# Decawave.net
KiCad netlist of a schematic drawn in Altium Designer
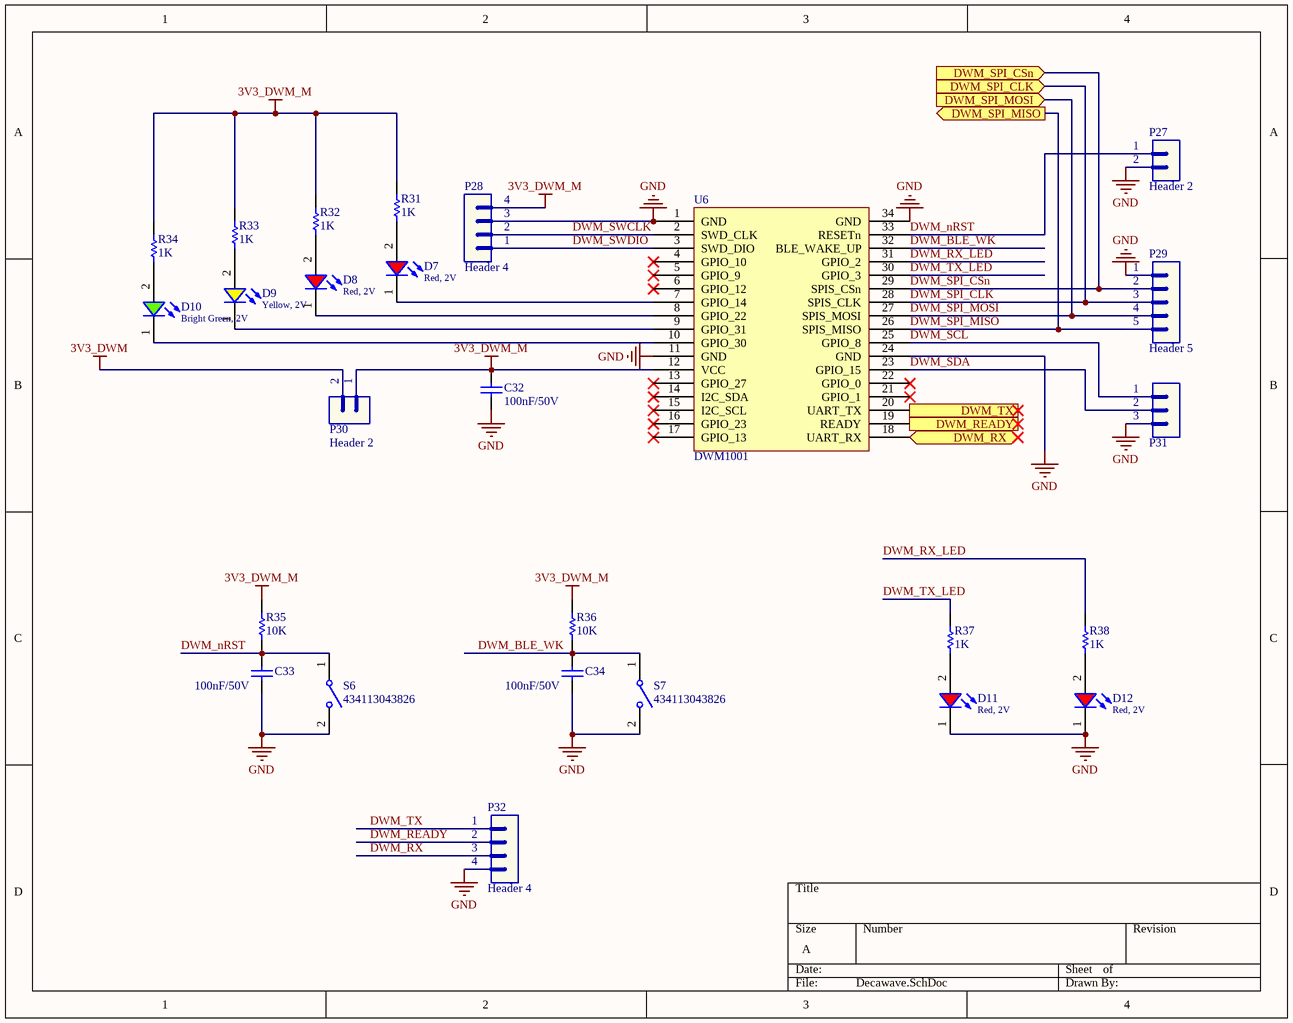
[diagram p0: Decawave.SchDoc]

(export (version "E")
  (design (tool "Eeschema 10.0.6"))
  (components
    (comp (ref "C32")
      (value "100nF/50V")
      (footprint "CAP-SM-0805")
      (description "CAP CER 0.1UF 50V Y5V 0805")
      (fields
        (field (name "MANUFACTURER") "Samsung Electro-Mechanics")
        (field (name "MANUFACTURER PART NUMBER") "CL21F104ZBCNNNC")
      )
      (libsource (lib "Capacitor") (part "Cap-100nF-50V-0805"))
    )
    (comp (ref "C33")
      (value "100nF/50V")
      (footprint "CAP-SM-0805")
      (description "CAP CER 0.1UF 50V Y5V 0805")
      (fields
        (field (name "MANUFACTURER") "Samsung Electro-Mechanics")
        (field (name "MANUFACTURER PART NUMBER") "CL21F104ZBCNNNC")
      )
      (libsource (lib "Capacitor") (part "Cap-100nF-50V-0805"))
    )
    (comp (ref "C34")
      (value "100nF/50V")
      (footprint "CAP-SM-0805")
      (description "CAP CER 0.1UF 50V Y5V 0805")
      (fields
        (field (name "MANUFACTURER") "Samsung Electro-Mechanics")
        (field (name "MANUFACTURER PART NUMBER") "CL21F104ZBCNNNC")
      )
      (libsource (lib "Capacitor") (part "Cap-100nF-50V-0805"))
    )
    (comp (ref "D7")
      (value "Red, 2V")
      (footprint "WL-SMCW_0805")
      (description "WL-SMCW SMT Mono-color Chip LED Waterclear, size 0805, Red, 2V, 140deg")
      (fields (field (name "PART NUMBER") "150080RS75000") (field (name "PUBLISHER") "Wurth Elektronik"))
      (libsource (lib "LED_150060BS75000_Altium_WL-SMCW_rev20a") (part "150080RS75000"))
    )
    (comp (ref "D8")
      (value "Red, 2V")
      (footprint "WL-SMCW_0805")
      (description "WL-SMCW SMT Mono-color Chip LED Waterclear, size 0805, Red, 2V, 140deg")
      (fields (field (name "PART NUMBER") "150080RS75000") (field (name "PUBLISHER") "Wurth Elektronik"))
      (libsource (lib "LED_150060BS75000_Altium_WL-SMCW_rev20a") (part "150080RS75000"))
    )
    (comp (ref "D9")
      (value "Yellow, 2V")
      (footprint "WL-SMCW_0805")
      (description "WL-SMCW SMT Mono-color Chip LED Waterclear, size 0805, Yellow, 2V, 140deg")
      (fields (field (name "PART NUMBER") "150080YS75000") (field (name "PUBLISHER") "Wurth Elektronik"))
      (libsource (lib "LED_150060BS75000_Altium_WL-SMCW_rev20a") (part "150080YS75000"))
    )
    (comp (ref "D10")
      (value "Bright Green, 2V")
      (footprint "WL-SMCW_0805")
      (description "WL-SMCW SMT Mono-color Chip LED Waterclear, size 0805, Bright Green, 2V, 140deg")
      (fields (field (name "PART NUMBER") "150080VS75000") (field (name "PUBLISHER") "Wurth Elektronik"))
      (libsource (lib "LED_150060BS75000_Altium_WL-SMCW_rev20a") (part "150080VS75000"))
    )
    (comp (ref "D11")
      (value "Red, 2V")
      (footprint "WL-SMCW_0805")
      (description "WL-SMCW SMT Mono-color Chip LED Waterclear, size 0805, Red, 2V, 140deg")
      (fields (field (name "PART NUMBER") "150080RS75000") (field (name "PUBLISHER") "Wurth Elektronik"))
      (libsource (lib "LED_150060BS75000_Altium_WL-SMCW_rev20a") (part "150080RS75000"))
    )
    (comp (ref "D12")
      (value "Red, 2V")
      (footprint "WL-SMCW_0805")
      (description "WL-SMCW SMT Mono-color Chip LED Waterclear, size 0805, Red, 2V, 140deg")
      (fields (field (name "PART NUMBER") "150080RS75000") (field (name "PUBLISHER") "Wurth Elektronik"))
      (libsource (lib "LED_150060BS75000_Altium_WL-SMCW_rev20a") (part "150080RS75000"))
    )
    (comp (ref "P27")
      (value "Header 2")
      (footprint "JP2")
      (description "Header, 2-Pin")
      (fields (field (name "PUBLISHER") "Altium Limited"))
      (libsource (lib "") (part "Header 2_1"))
    )
    (comp (ref "P28")
      (value "Header 4")
      (footprint "JP4")
      (description "Header, 4-Pin")
      (fields (field (name "PUBLISHER") "Altium Limited"))
      (libsource (lib "Header-connector") (part "Header 4"))
    )
    (comp (ref "P29")
      (value "Header 5")
      (footprint "JP5")
      (description "Header, 5-Pin")
      (fields (field (name "PUBLISHER") "Altium Limited"))
      (libsource (lib "Header-connector") (part "Header 5"))
    )
    (comp (ref "P30")
      (value "Header 2")
      (footprint "JP2")
      (description "Header, 2-Pin")
      (fields (field (name "PUBLISHER") "Altium Limited"))
      (libsource (lib "Header-connector") (part "Header 2"))
    )
    (comp (ref "P31")
      (value "Header 3")
      (footprint "JP3")
      (description "Header, 3-Pin")
      (fields (field (name "PUBLISHER") "Altium Limited"))
      (libsource (lib "Header-connector") (part "Header 3"))
    )
    (comp (ref "P32")
      (value "Header 4")
      (footprint "JP4")
      (description "Header, 4-Pin")
      (fields (field (name "PUBLISHER") "Altium Limited"))
      (libsource (lib "") (part "Header 4_1"))
    )
    (comp (ref "R31")
      (value "1K")
      (footprint "Resistor:RES-SM-0805")
      (description "RES 1K OHM 1% 1/4W 0805")
      (fields
        (field (name "MANUFACTURER") "Stackpole Electronics Inc")
        (field (name "MANUFACTURER PART NUMBER") "RNCP0805FTD1K00")
      )
      (libsource (lib "Resistor") (part "Res-1K-0805"))
    )
    (comp (ref "R32")
      (value "1K")
      (footprint "Resistor:RES-SM-0805")
      (description "RES 1K OHM 1% 1/4W 0805")
      (fields
        (field (name "MANUFACTURER") "Stackpole Electronics Inc")
        (field (name "MANUFACTURER PART NUMBER") "RNCP0805FTD1K00")
      )
      (libsource (lib "Resistor") (part "Res-1K-0805"))
    )
    (comp (ref "R33")
      (value "1K")
      (footprint "Resistor:RES-SM-0805")
      (description "RES 1K OHM 1% 1/4W 0805")
      (fields
        (field (name "MANUFACTURER") "Stackpole Electronics Inc")
        (field (name "MANUFACTURER PART NUMBER") "RNCP0805FTD1K00")
      )
      (libsource (lib "Resistor") (part "Res-1K-0805"))
    )
    (comp (ref "R34")
      (value "1K")
      (footprint "Resistor:RES-SM-0805")
      (description "RES 1K OHM 1% 1/4W 0805")
      (fields
        (field (name "MANUFACTURER") "Stackpole Electronics Inc")
        (field (name "MANUFACTURER PART NUMBER") "RNCP0805FTD1K00")
      )
      (libsource (lib "Resistor") (part "Res-1K-0805"))
    )
    (comp (ref "R35")
      (value "10K")
      (footprint "Resistor:RES-SM-0805")
      (description "RES 10K OHM 1% 1/4W 0805")
      (fields
        (field (name "MANUFACTURER") "Stackpole Electronics Inc")
        (field (name "MANUFACTURER PART NUMBER") "RNCP0805FTD10K0")
      )
      (libsource (lib "Resistor") (part "Res-10k-0805"))
    )
    (comp (ref "R36")
      (value "10K")
      (footprint "Resistor:RES-SM-0805")
      (description "RES 10K OHM 1% 1/4W 0805")
      (fields
        (field (name "MANUFACTURER") "Stackpole Electronics Inc")
        (field (name "MANUFACTURER PART NUMBER") "RNCP0805FTD10K0")
      )
      (libsource (lib "Resistor") (part "Res-10k-0805"))
    )
    (comp (ref "R37")
      (value "1K")
      (footprint "Resistor:RES-SM-0805")
      (description "RES 1K OHM 1% 1/4W 0805")
      (fields
        (field (name "MANUFACTURER") "Stackpole Electronics Inc")
        (field (name "MANUFACTURER PART NUMBER") "RNCP0805FTD1K00")
      )
      (libsource (lib "Resistor") (part "Res-1K-0805"))
    )
    (comp (ref "R38")
      (value "1K")
      (footprint "Resistor:RES-SM-0805")
      (description "RES 1K OHM 1% 1/4W 0805")
      (fields
        (field (name "MANUFACTURER") "Stackpole Electronics Inc")
        (field (name "MANUFACTURER PART NUMBER") "RNCP0805FTD1K00")
      )
      (libsource (lib "Resistor") (part "Res-1K-0805"))
    )
    (comp (ref "S6")
      (value "434113043826")
      (footprint "434113043826")
      (description "WS-TASV J-Bend SMT Tact Switch 6x3.5mm, height 4.3mm, 260gf")
      (fields (field (name "PUBLISHER") "Wurth Elektronik"))
      (libsource (lib "434113043826_Altium_WS-TASV_rev20a") (part "434113043826"))
    )
    (comp (ref "S7")
      (value "434113043826")
      (footprint "434113043826")
      (description "WS-TASV J-Bend SMT Tact Switch 6x3.5mm, height 4.3mm, 260gf")
      (fields (field (name "PUBLISHER") "Wurth Elektronik"))
      (libsource (lib "434113043826_Altium_WS-TASV_rev20a") (part "434113043826"))
    )
    (comp (ref "U6") (value "DWM1001") (footprint "DWM1001") (libsource (lib "PIFWRoBot") (part "DWM1001")))
  )
  (nets
    (net (code "1") (name "/DWM_BLE_WK") (class "Default")
      (node (ref "C34") (pin "1") (pinfunction "1_1") (pintype "passive"))
      (node (ref "R36") (pin "1") (pinfunction "1_1") (pintype "passive"))
      (node (ref "S7") (pin "1") (pinfunction "1_1") (pintype "passive"))
      (node (ref "U6") (pin "32") (pinfunction "BLE_WAKE_UP_32") (pintype "passive"))
    )
    (net (code "2") (name "/DWM_READY") (class "Default")
      (node (ref "P32") (pin "2") (pinfunction "2_2") (pintype "passive+no_connect"))
    )
    (net (code "3") (name "/DWM_RX") (class "Default")
      (node (ref "P32") (pin "3") (pinfunction "3_3") (pintype "passive+no_connect"))
    )
    (net (code "4") (name "/DWM_RX_LED") (class "Default")
      (node (ref "R38") (pin "2") (pinfunction "2_2") (pintype "passive"))
      (node (ref "U6") (pin "31") (pinfunction "GPIO_2_31") (pintype "passive"))
    )
    (net (code "5") (name "/DWM_SCL") (class "Default")
      (node (ref "P31") (pin "1") (pinfunction "1_1") (pintype "passive"))
      (node (ref "U6") (pin "25") (pinfunction "GPIO_8_25") (pintype "passive"))
    )
    (net (code "6") (name "/DWM_SDA") (class "Default")
      (node (ref "P31") (pin "2") (pinfunction "2_2") (pintype "passive"))
      (node (ref "U6") (pin "23") (pinfunction "GPIO_15_23") (pintype "passive"))
    )
    (net (code "7") (name "/DWM_SPI_CLK") (class "Default")
      (node (ref "P29") (pin "3") (pinfunction "3_3") (pintype "passive"))
      (node (ref "U6") (pin "28") (pinfunction "SPIS_CLK_28") (pintype "passive"))
    )
    (net (code "8") (name "/DWM_SPI_CSn") (class "Default")
      (node (ref "P29") (pin "2") (pinfunction "2_2") (pintype "passive"))
      (node (ref "U6") (pin "29") (pinfunction "SPIS_CSn_29") (pintype "passive"))
    )
    (net (code "9") (name "/DWM_SPI_MISO") (class "Default")
      (node (ref "P29") (pin "5") (pinfunction "5_5") (pintype "passive"))
      (node (ref "U6") (pin "26") (pinfunction "SPIS_MISO_26") (pintype "passive"))
    )
    (net (code "10") (name "/DWM_SPI_MOSI") (class "Default")
      (node (ref "P29") (pin "4") (pinfunction "4_4") (pintype "passive"))
      (node (ref "U6") (pin "27") (pinfunction "SPIS_MOSI_27") (pintype "passive"))
    )
    (net (code "11") (name "/DWM_SWCLK") (class "Default")
      (node (ref "P28") (pin "2") (pinfunction "2_2") (pintype "passive"))
      (node (ref "U6") (pin "2") (pinfunction "SWD_CLK_2") (pintype "passive"))
    )
    (net (code "12") (name "/DWM_SWDIO") (class "Default")
      (node (ref "P28") (pin "1") (pinfunction "1_1") (pintype "passive"))
      (node (ref "U6") (pin "3") (pinfunction "SWD_DIO_3") (pintype "passive"))
    )
    (net (code "13") (name "/DWM_TX") (class "Default")
      (node (ref "P32") (pin "1") (pinfunction "1_1") (pintype "passive+no_connect"))
    )
    (net (code "14") (name "/DWM_TX_LED") (class "Default")
      (node (ref "R37") (pin "2") (pinfunction "2_2") (pintype "passive"))
      (node (ref "U6") (pin "30") (pinfunction "GPIO_3_30") (pintype "passive"))
    )
    (net (code "15") (name "/DWM_nRST") (class "Default")
      (node (ref "C33") (pin "1") (pinfunction "1_1") (pintype "passive"))
      (node (ref "P27") (pin "1") (pinfunction "1_1") (pintype "passive"))
      (node (ref "R35") (pin "1") (pinfunction "1_1") (pintype "passive"))
      (node (ref "S6") (pin "1") (pinfunction "1_1") (pintype "passive"))
      (node (ref "U6") (pin "33") (pinfunction "RESETn_33") (pintype "passive"))
    )
    (net (code "16") (name "3V3_DWM") (class "Default")
      (node (ref "P30") (pin "2") (pinfunction "2_2") (pintype "passive"))
    )
    (net (code "17") (name "3V3_DWM_M") (class "Default")
      (node (ref "C32") (pin "2") (pinfunction "2_2") (pintype "passive"))
      (node (ref "P28") (pin "4") (pinfunction "4_4") (pintype "passive"))
      (node (ref "P30") (pin "1") (pinfunction "1_1") (pintype "passive"))
      (node (ref "R31") (pin "2") (pinfunction "2_2") (pintype "passive"))
      (node (ref "R32") (pin "2") (pinfunction "2_2") (pintype "passive"))
      (node (ref "R33") (pin "2") (pinfunction "2_2") (pintype "passive"))
      (node (ref "R34") (pin "2") (pinfunction "2_2") (pintype "passive"))
      (node (ref "R35") (pin "2") (pinfunction "2_2") (pintype "passive"))
      (node (ref "R36") (pin "2") (pinfunction "2_2") (pintype "passive"))
      (node (ref "U6") (pin "12") (pinfunction "VCC_12") (pintype "passive"))
    )
    (net (code "18") (name "GND") (class "Default")
      (node (ref "C32") (pin "1") (pinfunction "1_1") (pintype "passive"))
      (node (ref "C33") (pin "2") (pinfunction "2_2") (pintype "passive"))
      (node (ref "C34") (pin "2") (pinfunction "2_2") (pintype "passive"))
      (node (ref "D11") (pin "1") (pinfunction "K_1") (pintype "passive"))
      (node (ref "D12") (pin "1") (pinfunction "K_1") (pintype "passive"))
      (node (ref "P27") (pin "2") (pinfunction "2_2") (pintype "passive"))
      (node (ref "P28") (pin "3") (pinfunction "3_3") (pintype "passive"))
      (node (ref "P29") (pin "1") (pinfunction "1_1") (pintype "passive"))
      (node (ref "P31") (pin "3") (pinfunction "3_3") (pintype "passive"))
      (node (ref "P32") (pin "4") (pinfunction "4_4") (pintype "passive"))
      (node (ref "S6") (pin "2") (pinfunction "2_2") (pintype "passive"))
      (node (ref "S7") (pin "2") (pinfunction "2_2") (pintype "passive"))
      (node (ref "U6") (pin "1") (pinfunction "GND_1") (pintype "passive"))
      (node (ref "U6") (pin "11") (pinfunction "GND_11") (pintype "passive"))
      (node (ref "U6") (pin "24") (pinfunction "GND_24") (pintype "passive"))
      (node (ref "U6") (pin "34") (pinfunction "GND_34") (pintype "passive"))
    )
    (net (code "19") (name "Net-(D7-A)") (class "Default")
      (node (ref "D7") (pin "2") (pinfunction "A_2") (pintype "passive"))
      (node (ref "R31") (pin "1") (pinfunction "1_1") (pintype "passive"))
    )
    (net (code "20") (name "Net-(D7-K)") (class "Default")
      (node (ref "D7") (pin "1") (pinfunction "K_1") (pintype "passive"))
      (node (ref "U6") (pin "7") (pinfunction "GPIO_14_7") (pintype "passive"))
    )
    (net (code "21") (name "Net-(D8-A)") (class "Default")
      (node (ref "D8") (pin "2") (pinfunction "A_2") (pintype "passive"))
      (node (ref "R32") (pin "1") (pinfunction "1_1") (pintype "passive"))
    )
    (net (code "22") (name "Net-(D8-K)") (class "Default")
      (node (ref "D8") (pin "1") (pinfunction "K_1") (pintype "passive"))
      (node (ref "U6") (pin "8") (pinfunction "GPIO_22_8") (pintype "passive"))
    )
    (net (code "23") (name "Net-(D9-A)") (class "Default")
      (node (ref "D9") (pin "2") (pinfunction "A_2") (pintype "passive"))
      (node (ref "R33") (pin "1") (pinfunction "1_1") (pintype "passive"))
    )
    (net (code "24") (name "Net-(D9-K)") (class "Default")
      (node (ref "D9") (pin "1") (pinfunction "K_1") (pintype "passive"))
      (node (ref "U6") (pin "9") (pinfunction "GPIO_31_9") (pintype "passive"))
    )
    (net (code "25") (name "Net-(D10-A)") (class "Default")
      (node (ref "D10") (pin "2") (pinfunction "A_2") (pintype "passive"))
      (node (ref "R34") (pin "1") (pinfunction "1_1") (pintype "passive"))
    )
    (net (code "26") (name "Net-(D10-K)") (class "Default")
      (node (ref "D10") (pin "1") (pinfunction "K_1") (pintype "passive"))
      (node (ref "U6") (pin "10") (pinfunction "GPIO_30_10") (pintype "passive"))
    )
    (net (code "27") (name "Net-(D11-A)") (class "Default")
      (node (ref "D11") (pin "2") (pinfunction "A_2") (pintype "passive"))
      (node (ref "R37") (pin "1") (pinfunction "1_1") (pintype "passive"))
    )
    (net (code "28") (name "Net-(D12-A)") (class "Default")
      (node (ref "D12") (pin "2") (pinfunction "A_2") (pintype "passive"))
      (node (ref "R38") (pin "1") (pinfunction "1_1") (pintype "passive"))
    )
    (net (code "29") (name "unconnected-(U6-GPIO_0-Pad22)") (class "Default")
      (node (ref "U6") (pin "22") (pinfunction "GPIO_0_22") (pintype "passive+no_connect"))
    )
    (net (code "30") (name "unconnected-(U6-GPIO_1-Pad21)") (class "Default")
      (node (ref "U6") (pin "21") (pinfunction "GPIO_1_21") (pintype "passive+no_connect"))
    )
    (net (code "31") (name "unconnected-(U6-GPIO_9-Pad5)") (class "Default")
      (node (ref "U6") (pin "5") (pinfunction "GPIO_9_5") (pintype "passive+no_connect"))
    )
    (net (code "32") (name "unconnected-(U6-GPIO_10-Pad4)") (class "Default")
      (node (ref "U6") (pin "4") (pinfunction "GPIO_10_4") (pintype "passive+no_connect"))
    )
    (net (code "33") (name "unconnected-(U6-GPIO_12-Pad6)") (class "Default")
      (node (ref "U6") (pin "6") (pinfunction "GPIO_12_6") (pintype "passive+no_connect"))
    )
    (net (code "34") (name "unconnected-(U6-GPIO_13-Pad17)") (class "Default")
      (node (ref "U6") (pin "17") (pinfunction "GPIO_13_17") (pintype "passive+no_connect"))
    )
    (net (code "35") (name "unconnected-(U6-GPIO_23-Pad16)") (class "Default")
      (node (ref "U6") (pin "16") (pinfunction "GPIO_23_16") (pintype "passive+no_connect"))
    )
    (net (code "36") (name "unconnected-(U6-GPIO_27-Pad13)") (class "Default")
      (node (ref "U6") (pin "13") (pinfunction "GPIO_27_13") (pintype "passive+no_connect"))
    )
    (net (code "37") (name "unconnected-(U6-I2C_SCL-Pad15)") (class "Default")
      (node (ref "U6") (pin "15") (pinfunction "I2C_SCL_15") (pintype "passive+no_connect"))
    )
    (net (code "38") (name "unconnected-(U6-I2C_SDA-Pad14)") (class "Default")
      (node (ref "U6") (pin "14") (pinfunction "I2C_SDA_14") (pintype "passive+no_connect"))
    )
    (net (code "39") (name "unconnected-(U6-READY-Pad19)") (class "Default")
      (node (ref "U6") (pin "19") (pinfunction "READY_19") (pintype "passive"))
    )
    (net (code "40") (name "unconnected-(U6-UART_RX-Pad18)") (class "Default")
      (node (ref "U6") (pin "18") (pinfunction "UART_RX_18") (pintype "passive"))
    )
    (net (code "41") (name "unconnected-(U6-UART_TX-Pad20)") (class "Default")
      (node (ref "U6") (pin "20") (pinfunction "UART_TX_20") (pintype "passive"))
    )
  )
)
